# 9_-LPDDR4_SDRAM-1.net
KiCad netlist of a schematic drawn in Altium Designer
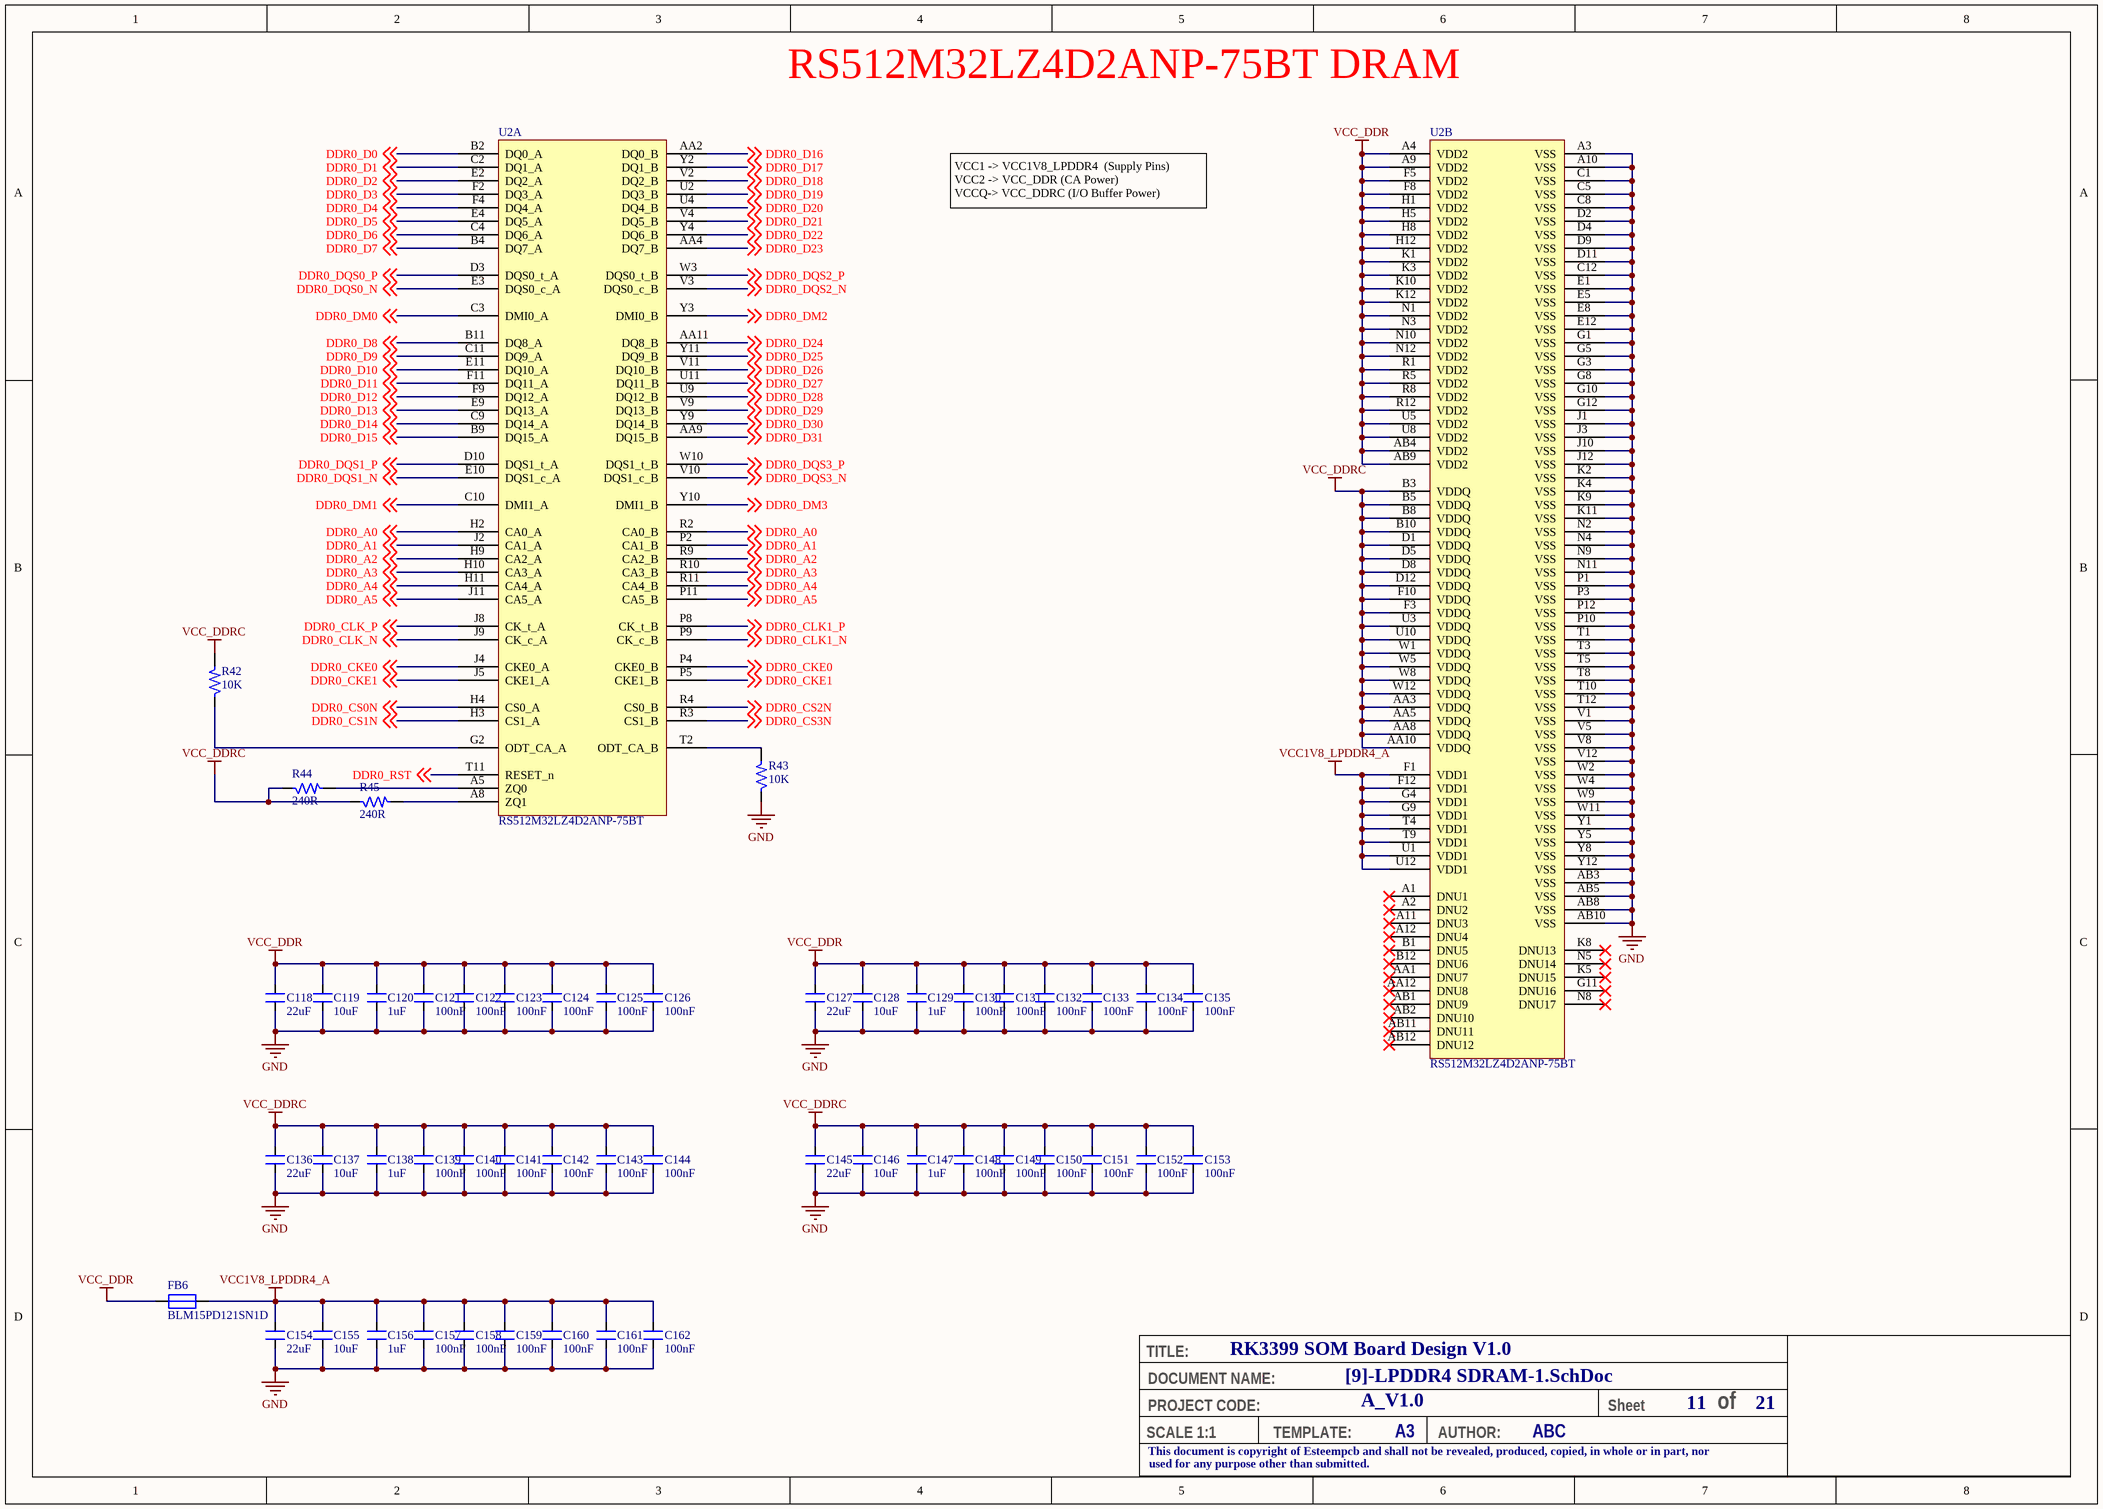
[diagram p0: [9]-LPDDR4 SDRAM-1.SchDoc]

(export (version "E")
  (design (tool "Eeschema 10.0.6"))
  (components
    (comp (ref "C118")
      (value "22uF")
      (footprint "CAP_0402")
      (description "22µF ±20% 6.3V Ceramic Capacitor X5R 0402 (1005 Metric)")
      (fields
        (field (name "MANUFACTURER") "Murata Electronics")
        (field (name "MANUFACTURER PART NUMBER") "CL05A226MQ5N6J8")
      )
      (libsource (lib "RK3399 _Module_Intlib") (part "CAP_22uF-6.3V-20%-0402"))
    )
    (comp (ref "C119")
      (value "10uF")
      (footprint "CAP_0402")
      (description "10µF ±20% 10V Ceramic Capacitor X5R 0402 (1005 Metric)")
      (fields
        (field (name "MANUFACTURER PART NUMBER") "CL05A106MP5NUNC")
        (field (name "MANUFACTURER") "Samsung Electro-Mechanics")
      )
      (libsource (lib "RK3399 _Module_Schlib") (part "CAP_10uF-10V-20%-0402"))
    )
    (comp (ref "C120")
      (value "1uF")
      (footprint "CAP_0201")
      (description "1µF ±20% 16V Ceramic Capacitor X5R 0201 (0603 Metric)")
      (fields
        (field (name "MANUFACTURER") "Samsung Electro-Mechanics")
        (field (name "MANUFACTURER PART NUMBER") "CL03A105MO3NRNH")
      )
      (libsource (lib "RK3399 _Module_Intlib") (part "CAP_1uF-16V-10%-0201"))
    )
    (comp (ref "C121")
      (value "100nF")
      (footprint "CAP_0201")
      (description "0.1µF ±10% 25V Ceramic Capacitor X5R 0201 (0603 Metric)")
      (fields
        (field (name "MANUFACTURER") "TDK Corporation")
        (field (name "MANUFACTURER PART NUMBER") "C0603X5R1E104K030BB")
      )
      (libsource (lib "RK3399 _Module_Intlib") (part "CAP_100nF-25V-10%-0201"))
    )
    (comp (ref "C122")
      (value "100nF")
      (footprint "CAP_0201")
      (description "0.1µF ±10% 25V Ceramic Capacitor X5R 0201 (0603 Metric)")
      (fields
        (field (name "MANUFACTURER") "TDK Corporation")
        (field (name "MANUFACTURER PART NUMBER") "C0603X5R1E104K030BB")
      )
      (libsource (lib "RK3399 _Module_Intlib") (part "CAP_100nF-25V-10%-0201"))
    )
    (comp (ref "C123")
      (value "100nF")
      (footprint "CAP_0201")
      (description "0.1µF ±10% 25V Ceramic Capacitor X5R 0201 (0603 Metric)")
      (fields
        (field (name "MANUFACTURER") "TDK Corporation")
        (field (name "MANUFACTURER PART NUMBER") "C0603X5R1E104K030BB")
      )
      (libsource (lib "RK3399 _Module_Intlib") (part "CAP_100nF-25V-10%-0201"))
    )
    (comp (ref "C124")
      (value "100nF")
      (footprint "CAP_0201")
      (description "0.1µF ±10% 25V Ceramic Capacitor X5R 0201 (0603 Metric)")
      (fields
        (field (name "MANUFACTURER") "TDK Corporation")
        (field (name "MANUFACTURER PART NUMBER") "C0603X5R1E104K030BB")
      )
      (libsource (lib "RK3399 _Module_Intlib") (part "CAP_100nF-25V-10%-0201"))
    )
    (comp (ref "C125")
      (value "100nF")
      (footprint "CAP_0201")
      (description "0.1µF ±10% 25V Ceramic Capacitor X5R 0201 (0603 Metric)")
      (fields
        (field (name "MANUFACTURER") "TDK Corporation")
        (field (name "MANUFACTURER PART NUMBER") "C0603X5R1E104K030BB")
      )
      (libsource (lib "RK3399 _Module_Intlib") (part "CAP_100nF-25V-10%-0201"))
    )
    (comp (ref "C126")
      (value "100nF")
      (footprint "CAP_0201")
      (description "0.1µF ±10% 25V Ceramic Capacitor X5R 0201 (0603 Metric)")
      (fields
        (field (name "MANUFACTURER") "TDK Corporation")
        (field (name "MANUFACTURER PART NUMBER") "C0603X5R1E104K030BB")
      )
      (libsource (lib "RK3399 _Module_Intlib") (part "CAP_100nF-25V-10%-0201"))
    )
    (comp (ref "C127")
      (value "22uF")
      (footprint "CAP_0402")
      (description "22µF ±20% 6.3V Ceramic Capacitor X5R 0402 (1005 Metric)")
      (fields
        (field (name "MANUFACTURER") "Murata Electronics")
        (field (name "MANUFACTURER PART NUMBER") "CL05A226MQ5N6J8")
      )
      (libsource (lib "RK3399 _Module_Intlib") (part "CAP_22uF-6.3V-20%-0402"))
    )
    (comp (ref "C128")
      (value "10uF")
      (footprint "CAP_0402")
      (description "10µF ±20% 10V Ceramic Capacitor X5R 0402 (1005 Metric)")
      (fields
        (field (name "MANUFACTURER PART NUMBER") "CL05A106MP5NUNC")
        (field (name "MANUFACTURER") "Samsung Electro-Mechanics")
      )
      (libsource (lib "RK3399 _Module_Schlib") (part "CAP_10uF-10V-20%-0402"))
    )
    (comp (ref "C129")
      (value "1uF")
      (footprint "CAP_0201")
      (description "1µF ±20% 16V Ceramic Capacitor X5R 0201 (0603 Metric)")
      (fields
        (field (name "MANUFACTURER") "Samsung Electro-Mechanics")
        (field (name "MANUFACTURER PART NUMBER") "CL03A105MO3NRNH")
      )
      (libsource (lib "RK3399 _Module_Intlib") (part "CAP_1uF-16V-10%-0201"))
    )
    (comp (ref "C130")
      (value "100nF")
      (footprint "CAP_0201")
      (description "0.1µF ±10% 25V Ceramic Capacitor X5R 0201 (0603 Metric)")
      (fields
        (field (name "MANUFACTURER") "TDK Corporation")
        (field (name "MANUFACTURER PART NUMBER") "C0603X5R1E104K030BB")
      )
      (libsource (lib "RK3399 _Module_Intlib") (part "CAP_100nF-25V-10%-0201"))
    )
    (comp (ref "C131")
      (value "100nF")
      (footprint "CAP_0201")
      (description "0.1µF ±10% 25V Ceramic Capacitor X5R 0201 (0603 Metric)")
      (fields
        (field (name "MANUFACTURER") "TDK Corporation")
        (field (name "MANUFACTURER PART NUMBER") "C0603X5R1E104K030BB")
      )
      (libsource (lib "RK3399 _Module_Intlib") (part "CAP_100nF-25V-10%-0201"))
    )
    (comp (ref "C132")
      (value "100nF")
      (footprint "CAP_0201")
      (description "0.1µF ±10% 25V Ceramic Capacitor X5R 0201 (0603 Metric)")
      (fields
        (field (name "MANUFACTURER") "TDK Corporation")
        (field (name "MANUFACTURER PART NUMBER") "C0603X5R1E104K030BB")
      )
      (libsource (lib "RK3399 _Module_Intlib") (part "CAP_100nF-25V-10%-0201"))
    )
    (comp (ref "C133")
      (value "100nF")
      (footprint "CAP_0201")
      (description "0.1µF ±10% 25V Ceramic Capacitor X5R 0201 (0603 Metric)")
      (fields
        (field (name "MANUFACTURER") "TDK Corporation")
        (field (name "MANUFACTURER PART NUMBER") "C0603X5R1E104K030BB")
      )
      (libsource (lib "RK3399 _Module_Intlib") (part "CAP_100nF-25V-10%-0201"))
    )
    (comp (ref "C134")
      (value "100nF")
      (footprint "CAP_0201")
      (description "0.1µF ±10% 25V Ceramic Capacitor X5R 0201 (0603 Metric)")
      (fields
        (field (name "MANUFACTURER") "TDK Corporation")
        (field (name "MANUFACTURER PART NUMBER") "C0603X5R1E104K030BB")
      )
      (libsource (lib "RK3399 _Module_Intlib") (part "CAP_100nF-25V-10%-0201"))
    )
    (comp (ref "C135")
      (value "100nF")
      (footprint "CAP_0201")
      (description "0.1µF ±10% 25V Ceramic Capacitor X5R 0201 (0603 Metric)")
      (fields
        (field (name "MANUFACTURER") "TDK Corporation")
        (field (name "MANUFACTURER PART NUMBER") "C0603X5R1E104K030BB")
      )
      (libsource (lib "RK3399 _Module_Intlib") (part "CAP_100nF-25V-10%-0201"))
    )
    (comp (ref "C136")
      (value "22uF")
      (footprint "CAP_0402")
      (description "22µF ±20% 6.3V Ceramic Capacitor X5R 0402 (1005 Metric)")
      (fields
        (field (name "MANUFACTURER") "Murata Electronics")
        (field (name "MANUFACTURER PART NUMBER") "CL05A226MQ5N6J8")
      )
      (libsource (lib "RK3399 _Module_Intlib") (part "CAP_22uF-6.3V-20%-0402"))
    )
    (comp (ref "C137")
      (value "10uF")
      (footprint "CAP_0402")
      (description "10µF ±20% 10V Ceramic Capacitor X5R 0402 (1005 Metric)")
      (fields
        (field (name "MANUFACTURER PART NUMBER") "CL05A106MP5NUNC")
        (field (name "MANUFACTURER") "Samsung Electro-Mechanics")
      )
      (libsource (lib "RK3399 _Module_Schlib") (part "CAP_10uF-10V-20%-0402"))
    )
    (comp (ref "C138")
      (value "1uF")
      (footprint "CAP_0201")
      (description "1µF ±20% 16V Ceramic Capacitor X5R 0201 (0603 Metric)")
      (fields
        (field (name "MANUFACTURER") "Samsung Electro-Mechanics")
        (field (name "MANUFACTURER PART NUMBER") "CL03A105MO3NRNH")
      )
      (libsource (lib "RK3399 _Module_Intlib") (part "CAP_1uF-16V-10%-0201"))
    )
    (comp (ref "C139")
      (value "100nF")
      (footprint "CAP_0201")
      (description "0.1µF ±10% 25V Ceramic Capacitor X5R 0201 (0603 Metric)")
      (fields
        (field (name "MANUFACTURER") "TDK Corporation")
        (field (name "MANUFACTURER PART NUMBER") "C0603X5R1E104K030BB")
      )
      (libsource (lib "RK3399 _Module_Intlib") (part "CAP_100nF-25V-10%-0201"))
    )
    (comp (ref "C140")
      (value "100nF")
      (footprint "CAP_0201")
      (description "0.1µF ±10% 25V Ceramic Capacitor X5R 0201 (0603 Metric)")
      (fields
        (field (name "MANUFACTURER") "TDK Corporation")
        (field (name "MANUFACTURER PART NUMBER") "C0603X5R1E104K030BB")
      )
      (libsource (lib "RK3399 _Module_Intlib") (part "CAP_100nF-25V-10%-0201"))
    )
    (comp (ref "C141")
      (value "100nF")
      (footprint "CAP_0201")
      (description "0.1µF ±10% 25V Ceramic Capacitor X5R 0201 (0603 Metric)")
      (fields
        (field (name "MANUFACTURER") "TDK Corporation")
        (field (name "MANUFACTURER PART NUMBER") "C0603X5R1E104K030BB")
      )
      (libsource (lib "RK3399 _Module_Intlib") (part "CAP_100nF-25V-10%-0201"))
    )
    (comp (ref "C142")
      (value "100nF")
      (footprint "CAP_0201")
      (description "0.1µF ±10% 25V Ceramic Capacitor X5R 0201 (0603 Metric)")
      (fields
        (field (name "MANUFACTURER") "TDK Corporation")
        (field (name "MANUFACTURER PART NUMBER") "C0603X5R1E104K030BB")
      )
      (libsource (lib "RK3399 _Module_Intlib") (part "CAP_100nF-25V-10%-0201"))
    )
    (comp (ref "C143")
      (value "100nF")
      (footprint "CAP_0201")
      (description "0.1µF ±10% 25V Ceramic Capacitor X5R 0201 (0603 Metric)")
      (fields
        (field (name "MANUFACTURER") "TDK Corporation")
        (field (name "MANUFACTURER PART NUMBER") "C0603X5R1E104K030BB")
      )
      (libsource (lib "RK3399 _Module_Intlib") (part "CAP_100nF-25V-10%-0201"))
    )
    (comp (ref "C144")
      (value "100nF")
      (footprint "CAP_0201")
      (description "0.1µF ±10% 25V Ceramic Capacitor X5R 0201 (0603 Metric)")
      (fields
        (field (name "MANUFACTURER") "TDK Corporation")
        (field (name "MANUFACTURER PART NUMBER") "C0603X5R1E104K030BB")
      )
      (libsource (lib "RK3399 _Module_Intlib") (part "CAP_100nF-25V-10%-0201"))
    )
    (comp (ref "C145")
      (value "22uF")
      (footprint "CAP_0402")
      (description "22µF ±20% 6.3V Ceramic Capacitor X5R 0402 (1005 Metric)")
      (fields
        (field (name "MANUFACTURER") "Murata Electronics")
        (field (name "MANUFACTURER PART NUMBER") "CL05A226MQ5N6J8")
      )
      (libsource (lib "RK3399 _Module_Intlib") (part "CAP_22uF-6.3V-20%-0402"))
    )
    (comp (ref "C146")
      (value "10uF")
      (footprint "CAP_0402")
      (description "10µF ±20% 10V Ceramic Capacitor X5R 0402 (1005 Metric)")
      (fields
        (field (name "MANUFACTURER PART NUMBER") "CL05A106MP5NUNC")
        (field (name "MANUFACTURER") "Samsung Electro-Mechanics")
      )
      (libsource (lib "RK3399 _Module_Schlib") (part "CAP_10uF-10V-20%-0402"))
    )
    (comp (ref "C147")
      (value "1uF")
      (footprint "CAP_0201")
      (description "1µF ±20% 16V Ceramic Capacitor X5R 0201 (0603 Metric)")
      (fields
        (field (name "MANUFACTURER") "Samsung Electro-Mechanics")
        (field (name "MANUFACTURER PART NUMBER") "CL03A105MO3NRNH")
      )
      (libsource (lib "RK3399 _Module_Intlib") (part "CAP_1uF-16V-10%-0201"))
    )
    (comp (ref "C148")
      (value "100nF")
      (footprint "CAP_0201")
      (description "0.1µF ±10% 25V Ceramic Capacitor X5R 0201 (0603 Metric)")
      (fields
        (field (name "MANUFACTURER") "TDK Corporation")
        (field (name "MANUFACTURER PART NUMBER") "C0603X5R1E104K030BB")
      )
      (libsource (lib "RK3399 _Module_Intlib") (part "CAP_100nF-25V-10%-0201"))
    )
    (comp (ref "C149")
      (value "100nF")
      (footprint "CAP_0201")
      (description "0.1µF ±10% 25V Ceramic Capacitor X5R 0201 (0603 Metric)")
      (fields
        (field (name "MANUFACTURER") "TDK Corporation")
        (field (name "MANUFACTURER PART NUMBER") "C0603X5R1E104K030BB")
      )
      (libsource (lib "RK3399 _Module_Intlib") (part "CAP_100nF-25V-10%-0201"))
    )
    (comp (ref "C150")
      (value "100nF")
      (footprint "CAP_0201")
      (description "0.1µF ±10% 25V Ceramic Capacitor X5R 0201 (0603 Metric)")
      (fields
        (field (name "MANUFACTURER") "TDK Corporation")
        (field (name "MANUFACTURER PART NUMBER") "C0603X5R1E104K030BB")
      )
      (libsource (lib "RK3399 _Module_Intlib") (part "CAP_100nF-25V-10%-0201"))
    )
    (comp (ref "C151")
      (value "100nF")
      (footprint "CAP_0201")
      (description "0.1µF ±10% 25V Ceramic Capacitor X5R 0201 (0603 Metric)")
      (fields
        (field (name "MANUFACTURER") "TDK Corporation")
        (field (name "MANUFACTURER PART NUMBER") "C0603X5R1E104K030BB")
      )
      (libsource (lib "RK3399 _Module_Intlib") (part "CAP_100nF-25V-10%-0201"))
    )
    (comp (ref "C152")
      (value "100nF")
      (footprint "CAP_0201")
      (description "0.1µF ±10% 25V Ceramic Capacitor X5R 0201 (0603 Metric)")
      (fields
        (field (name "MANUFACTURER") "TDK Corporation")
        (field (name "MANUFACTURER PART NUMBER") "C0603X5R1E104K030BB")
      )
      (libsource (lib "RK3399 _Module_Intlib") (part "CAP_100nF-25V-10%-0201"))
    )
    (comp (ref "C153")
      (value "100nF")
      (footprint "CAP_0201")
      (description "0.1µF ±10% 25V Ceramic Capacitor X5R 0201 (0603 Metric)")
      (fields
        (field (name "MANUFACTURER") "TDK Corporation")
        (field (name "MANUFACTURER PART NUMBER") "C0603X5R1E104K030BB")
      )
      (libsource (lib "RK3399 _Module_Intlib") (part "CAP_100nF-25V-10%-0201"))
    )
    (comp (ref "C154")
      (value "22uF")
      (footprint "CAP_0402")
      (description "22µF ±20% 6.3V Ceramic Capacitor X5R 0402 (1005 Metric)")
      (fields
        (field (name "MANUFACTURER") "Murata Electronics")
        (field (name "MANUFACTURER PART NUMBER") "CL05A226MQ5N6J8")
      )
      (libsource (lib "RK3399 _Module_Intlib") (part "CAP_22uF-6.3V-20%-0402"))
    )
    (comp (ref "C155")
      (value "10uF")
      (footprint "CAP_0402")
      (description "10µF ±20% 10V Ceramic Capacitor X5R 0402 (1005 Metric)")
      (fields
        (field (name "MANUFACTURER PART NUMBER") "CL05A106MP5NUNC")
        (field (name "MANUFACTURER") "Samsung Electro-Mechanics")
      )
      (libsource (lib "RK3399 _Module_Schlib") (part "CAP_10uF-10V-20%-0402"))
    )
    (comp (ref "C156")
      (value "1uF")
      (footprint "CAP_0201")
      (description "1µF ±20% 16V Ceramic Capacitor X5R 0201 (0603 Metric)")
      (fields
        (field (name "MANUFACTURER") "Samsung Electro-Mechanics")
        (field (name "MANUFACTURER PART NUMBER") "CL03A105MO3NRNH")
      )
      (libsource (lib "RK3399 _Module_Intlib") (part "CAP_1uF-16V-10%-0201"))
    )
    (comp (ref "C157")
      (value "100nF")
      (footprint "CAP_0201")
      (description "0.1µF ±10% 25V Ceramic Capacitor X5R 0201 (0603 Metric)")
      (fields
        (field (name "MANUFACTURER") "TDK Corporation")
        (field (name "MANUFACTURER PART NUMBER") "C0603X5R1E104K030BB")
      )
      (libsource (lib "RK3399 _Module_Intlib") (part "CAP_100nF-25V-10%-0201"))
    )
    (comp (ref "C158")
      (value "100nF")
      (footprint "CAP_0201")
      (description "0.1µF ±10% 25V Ceramic Capacitor X5R 0201 (0603 Metric)")
      (fields
        (field (name "MANUFACTURER") "TDK Corporation")
        (field (name "MANUFACTURER PART NUMBER") "C0603X5R1E104K030BB")
      )
      (libsource (lib "RK3399 _Module_Intlib") (part "CAP_100nF-25V-10%-0201"))
    )
    (comp (ref "C159")
      (value "100nF")
      (footprint "CAP_0201")
      (description "0.1µF ±10% 25V Ceramic Capacitor X5R 0201 (0603 Metric)")
      (fields
        (field (name "MANUFACTURER") "TDK Corporation")
        (field (name "MANUFACTURER PART NUMBER") "C0603X5R1E104K030BB")
      )
      (libsource (lib "RK3399 _Module_Intlib") (part "CAP_100nF-25V-10%-0201"))
    )
    (comp (ref "C160")
      (value "100nF")
      (footprint "CAP_0201")
      (description "0.1µF ±10% 25V Ceramic Capacitor X5R 0201 (0603 Metric)")
      (fields
        (field (name "MANUFACTURER") "TDK Corporation")
        (field (name "MANUFACTURER PART NUMBER") "C0603X5R1E104K030BB")
      )
      (libsource (lib "RK3399 _Module_Intlib") (part "CAP_100nF-25V-10%-0201"))
    )
    (comp (ref "C161")
      (value "100nF")
      (footprint "CAP_0201")
      (description "0.1µF ±10% 25V Ceramic Capacitor X5R 0201 (0603 Metric)")
      (fields
        (field (name "MANUFACTURER") "TDK Corporation")
        (field (name "MANUFACTURER PART NUMBER") "C0603X5R1E104K030BB")
      )
      (libsource (lib "RK3399 _Module_Intlib") (part "CAP_100nF-25V-10%-0201"))
    )
    (comp (ref "C162")
      (value "100nF")
      (footprint "CAP_0201")
      (description "0.1µF ±10% 25V Ceramic Capacitor X5R 0201 (0603 Metric)")
      (fields
        (field (name "MANUFACTURER") "TDK Corporation")
        (field (name "MANUFACTURER PART NUMBER") "C0603X5R1E104K030BB")
      )
      (libsource (lib "RK3399 _Module_Intlib") (part "CAP_100nF-25V-10%-0201"))
    )
    (comp (ref "FB6")
      (value "BLM15PD121SN1D")
      (footprint "RES_0402")
      (description "120 Ohms @ 100MHz 1 Power Line Ferrite Bead 0402 (1005 Metric) 1.3A 90mOhm")
      (fields (field (name "MANUFACTURER") "Murata Electronics"))
      (libsource (lib "RK3399 _Module_Schlib") (part "FB_120R-1.3A-100Mhz-0402"))
    )
    (comp (ref "R42")
      (value "10K")
      (footprint "RES_0201")
      (description "10 kOhms ±1% 0.05W, 1/20W Chip Resistor 0201 (0603 Metric) Thick Film")
      (fields
        (field (name "MANUFACTURER") "Stackpole Electronics Inc")
        (field (name "MANUFACTURER PART NUMBER") "RMCF0201FT10K0")
      )
      (libsource (lib "RK3399 _Module_Intlib") (part "RES_10K-0.05W-1%-0201"))
    )
    (comp (ref "R43")
      (value "10K")
      (footprint "RES_0201")
      (description "10 kOhms ±1% 0.05W, 1/20W Chip Resistor 0201 (0603 Metric) Thick Film")
      (fields
        (field (name "MANUFACTURER") "Stackpole Electronics Inc")
        (field (name "MANUFACTURER PART NUMBER") "RMCF0201FT10K0")
      )
      (libsource (lib "RK3399 _Module_Intlib") (part "RES_10K-0.05W-1%-0201"))
    )
    (comp (ref "R44")
      (value "240R")
      (footprint "RES_0201")
      (description "240 Ohms ±1% 0.05W, 1/20W Chip Resistor 0201 (0603 Metric) Thick Film")
      (fields
        (field (name "MANUFACTURER") "Yageo")
        (field (name "MANUFACTURER PART NUMBER") "RC0201FR-07240RL")
      )
      (libsource (lib "RK3399 _Module_Intlib") (part "RES_240R-0.05W-1%-0201"))
    )
    (comp (ref "R45")
      (value "240R")
      (footprint "RES_0201")
      (description "240 Ohms ±1% 0.05W, 1/20W Chip Resistor 0201 (0603 Metric) Thick Film")
      (fields
        (field (name "MANUFACTURER") "Yageo")
        (field (name "MANUFACTURER PART NUMBER") "RC0201FR-07240RL")
      )
      (libsource (lib "RK3399 _Module_Intlib") (part "RES_240R-0.05W-1%-0201"))
    )
    (comp (ref "U2")
      (value "RS512M32LZ4D2ANP-75BT")
      (footprint "FBGA200_SMD")
      (fields (field (name "MANUFACTURER") "RAYSON"))
      (libsource (lib "RK3399 _Module_Schlib") (part "IC_RS512M32LZ4D2ANP-75BT"))
    )
  )
  (nets
    (net (code "1") (name "DDR0_A0") (class "Default")
      (node (ref "U2") (pin "H2") (pinfunction "CA0_A_H2") (pintype "passive"))
      (node (ref "U2") (pin "R2") (pinfunction "CA0_B_R2") (pintype "passive"))
    )
    (net (code "2") (name "DDR0_A1") (class "Default")
      (node (ref "U2") (pin "J2") (pinfunction "CA1_A_J2") (pintype "passive"))
      (node (ref "U2") (pin "P2") (pinfunction "CA1_B_P2") (pintype "passive"))
    )
    (net (code "3") (name "DDR0_A2") (class "Default")
      (node (ref "U2") (pin "H9") (pinfunction "CA2_A_H9") (pintype "passive"))
      (node (ref "U2") (pin "R9") (pinfunction "CA2_B_R9") (pintype "passive"))
    )
    (net (code "4") (name "DDR0_A3") (class "Default")
      (node (ref "U2") (pin "H10") (pinfunction "CA3_A_H10") (pintype "passive"))
      (node (ref "U2") (pin "R10") (pinfunction "CA3_B_R10") (pintype "passive"))
    )
    (net (code "5") (name "DDR0_A4") (class "Default")
      (node (ref "U2") (pin "H11") (pinfunction "CA4_A_H11") (pintype "passive"))
      (node (ref "U2") (pin "R11") (pinfunction "CA4_B_R11") (pintype "passive"))
    )
    (net (code "6") (name "DDR0_A5") (class "Default")
      (node (ref "U2") (pin "J11") (pinfunction "CA5_A_J11") (pintype "passive"))
      (node (ref "U2") (pin "P11") (pinfunction "CA5_B_P11") (pintype "passive"))
    )
    (net (code "7") (name "DDR0_CKE0") (class "Default")
      (node (ref "U2") (pin "J4") (pinfunction "CKE0_A_J4") (pintype "passive"))
      (node (ref "U2") (pin "P4") (pinfunction "CKE0_B_P4") (pintype "passive"))
    )
    (net (code "8") (name "DDR0_CKE1") (class "Default")
      (node (ref "U2") (pin "J5") (pinfunction "CKE1_A_J5") (pintype "passive"))
      (node (ref "U2") (pin "P5") (pinfunction "CKE1_B_P5") (pintype "passive"))
    )
    (net (code "9") (name "DDR0_CLK1_N") (class "Default")
      (node (ref "U2") (pin "P9") (pinfunction "CK_c_B_P9") (pintype "passive"))
    )
    (net (code "10") (name "DDR0_CLK1_P") (class "Default")
      (node (ref "U2") (pin "P8") (pinfunction "CK_t_B_P8") (pintype "passive"))
    )
    (net (code "11") (name "DDR0_CLK_N") (class "Default")
      (node (ref "U2") (pin "J9") (pinfunction "CK_c_A_J9") (pintype "passive"))
    )
    (net (code "12") (name "DDR0_CLK_P") (class "Default")
      (node (ref "U2") (pin "J8") (pinfunction "CK_t_A_J8") (pintype "passive"))
    )
    (net (code "13") (name "DDR0_CS0N") (class "Default")
      (node (ref "U2") (pin "H4") (pinfunction "CS0_A_H4") (pintype "passive"))
    )
    (net (code "14") (name "DDR0_CS1N") (class "Default")
      (node (ref "U2") (pin "H3") (pinfunction "CS1_A_H3") (pintype "passive"))
    )
    (net (code "15") (name "DDR0_CS2N") (class "Default")
      (node (ref "U2") (pin "R4") (pinfunction "CS0_B_R4") (pintype "passive"))
    )
    (net (code "16") (name "DDR0_CS3N") (class "Default")
      (node (ref "U2") (pin "R3") (pinfunction "CS1_B_R3") (pintype "passive"))
    )
    (net (code "17") (name "DDR0_D0") (class "Default")
      (node (ref "U2") (pin "B2") (pinfunction "DQ0_A_B2") (pintype "passive"))
    )
    (net (code "18") (name "DDR0_D1") (class "Default")
      (node (ref "U2") (pin "C2") (pinfunction "DQ1_A_C2") (pintype "passive"))
    )
    (net (code "19") (name "DDR0_D2") (class "Default")
      (node (ref "U2") (pin "E2") (pinfunction "DQ2_A_E2") (pintype "passive"))
    )
    (net (code "20") (name "DDR0_D3") (class "Default")
      (node (ref "U2") (pin "F2") (pinfunction "DQ3_A_F2") (pintype "passive"))
    )
    (net (code "21") (name "DDR0_D4") (class "Default")
      (node (ref "U2") (pin "F4") (pinfunction "DQ4_A_F4") (pintype "passive"))
    )
    (net (code "22") (name "DDR0_D5") (class "Default")
      (node (ref "U2") (pin "E4") (pinfunction "DQ5_A_E4") (pintype "passive"))
    )
    (net (code "23") (name "DDR0_D6") (class "Default")
      (node (ref "U2") (pin "C4") (pinfunction "DQ6_A_C4") (pintype "passive"))
    )
    (net (code "24") (name "DDR0_D7") (class "Default")
      (node (ref "U2") (pin "B4") (pinfunction "DQ7_A_B4") (pintype "passive"))
    )
    (net (code "25") (name "DDR0_D8") (class "Default")
      (node (ref "U2") (pin "B11") (pinfunction "DQ8_A_B11") (pintype "passive"))
    )
    (net (code "26") (name "DDR0_D9") (class "Default")
      (node (ref "U2") (pin "C11") (pinfunction "DQ9_A_C11") (pintype "passive"))
    )
    (net (code "27") (name "DDR0_D10") (class "Default")
      (node (ref "U2") (pin "E11") (pinfunction "DQ10_A_E11") (pintype "passive"))
    )
    (net (code "28") (name "DDR0_D11") (class "Default")
      (node (ref "U2") (pin "F11") (pinfunction "DQ11_A_F11") (pintype "passive"))
    )
    (net (code "29") (name "DDR0_D12") (class "Default")
      (node (ref "U2") (pin "F9") (pinfunction "DQ12_A_F9") (pintype "passive"))
    )
    (net (code "30") (name "DDR0_D13") (class "Default")
      (node (ref "U2") (pin "E9") (pinfunction "DQ13_A_E9") (pintype "passive"))
    )
    (net (code "31") (name "DDR0_D14") (class "Default")
      (node (ref "U2") (pin "C9") (pinfunction "DQ14_A_C9") (pintype "passive"))
    )
    (net (code "32") (name "DDR0_D15") (class "Default")
      (node (ref "U2") (pin "B9") (pinfunction "DQ15_A_B9") (pintype "passive"))
    )
    (net (code "33") (name "DDR0_D16") (class "Default")
      (node (ref "U2") (pin "AA2") (pinfunction "DQ0_B_AA2") (pintype "passive"))
    )
    (net (code "34") (name "DDR0_D17") (class "Default")
      (node (ref "U2") (pin "Y2") (pinfunction "DQ1_B_Y2") (pintype "passive"))
    )
    (net (code "35") (name "DDR0_D18") (class "Default")
      (node (ref "U2") (pin "V2") (pinfunction "DQ2_B_V2") (pintype "passive"))
    )
    (net (code "36") (name "DDR0_D19") (class "Default")
      (node (ref "U2") (pin "U2") (pinfunction "DQ3_B_U2") (pintype "passive"))
    )
    (net (code "37") (name "DDR0_D20") (class "Default")
      (node (ref "U2") (pin "U4") (pinfunction "DQ4_B_U4") (pintype "passive"))
    )
    (net (code "38") (name "DDR0_D21") (class "Default")
      (node (ref "U2") (pin "V4") (pinfunction "DQ5_B_V4") (pintype "passive"))
    )
    (net (code "39") (name "DDR0_D22") (class "Default")
      (node (ref "U2") (pin "Y4") (pinfunction "DQ6_B_Y4") (pintype "passive"))
    )
    (net (code "40") (name "DDR0_D23") (class "Default")
      (node (ref "U2") (pin "AA4") (pinfunction "DQ7_B_AA4") (pintype "passive"))
    )
    (net (code "41") (name "DDR0_D24") (class "Default")
      (node (ref "U2") (pin "AA11") (pinfunction "DQ8_B_AA11") (pintype "passive"))
    )
    (net (code "42") (name "DDR0_D25") (class "Default")
      (node (ref "U2") (pin "Y11") (pinfunction "DQ9_B_Y11") (pintype "passive"))
    )
    (net (code "43") (name "DDR0_D26") (class "Default")
      (node (ref "U2") (pin "V11") (pinfunction "DQ10_B_V11") (pintype "passive"))
    )
    (net (code "44") (name "DDR0_D27") (class "Default")
      (node (ref "U2") (pin "U11") (pinfunction "DQ11_B_U11") (pintype "passive"))
    )
    (net (code "45") (name "DDR0_D28") (class "Default")
      (node (ref "U2") (pin "U9") (pinfunction "DQ12_B_U9") (pintype "passive"))
    )
    (net (code "46") (name "DDR0_D29") (class "Default")
      (node (ref "U2") (pin "V9") (pinfunction "DQ13_B_V9") (pintype "passive"))
    )
    (net (code "47") (name "DDR0_D30") (class "Default")
      (node (ref "U2") (pin "Y9") (pinfunction "DQ14_B_Y9") (pintype "passive"))
    )
    (net (code "48") (name "DDR0_D31") (class "Default")
      (node (ref "U2") (pin "AA9") (pinfunction "DQ15_B_AA9") (pintype "passive"))
    )
    (net (code "49") (name "DDR0_DM0") (class "Default")
      (node (ref "U2") (pin "C3") (pinfunction "DMI0_A_C3") (pintype "passive"))
    )
    (net (code "50") (name "DDR0_DM1") (class "Default")
      (node (ref "U2") (pin "C10") (pinfunction "DMI1_A_C10") (pintype "passive"))
    )
    (net (code "51") (name "DDR0_DM2") (class "Default")
      (node (ref "U2") (pin "Y3") (pinfunction "DMI0_B_Y3") (pintype "passive"))
    )
    (net (code "52") (name "DDR0_DM3") (class "Default")
      (node (ref "U2") (pin "Y10") (pinfunction "DMI1_B_Y10") (pintype "passive"))
    )
    (net (code "53") (name "DDR0_DQS0_N") (class "Default")
      (node (ref "U2") (pin "E3") (pinfunction "DQS0_c_A_E3") (pintype "passive"))
    )
    (net (code "54") (name "DDR0_DQS0_P") (class "Default")
      (node (ref "U2") (pin "D3") (pinfunction "DQS0_t_A_D3") (pintype "passive"))
    )
    (net (code "55") (name "DDR0_DQS1_N") (class "Default")
      (node (ref "U2") (pin "E10") (pinfunction "DQS1_c_A_E10") (pintype "passive"))
    )
    (net (code "56") (name "DDR0_DQS1_P") (class "Default")
      (node (ref "U2") (pin "D10") (pinfunction "DQS1_t_A_D10") (pintype "passive"))
    )
    (net (code "57") (name "DDR0_DQS2_N") (class "Default")
      (node (ref "U2") (pin "V3") (pinfunction "DQS0_c_B_V3") (pintype "passive"))
    )
    (net (code "58") (name "DDR0_DQS2_P") (class "Default")
      (node (ref "U2") (pin "W3") (pinfunction "DQS0_t_B_W3") (pintype "passive"))
    )
    (net (code "59") (name "DDR0_DQS3_N") (class "Default")
      (node (ref "U2") (pin "V10") (pinfunction "DQS1_c_B_V10") (pintype "passive"))
    )
    (net (code "60") (name "DDR0_DQS3_P") (class "Default")
      (node (ref "U2") (pin "W10") (pinfunction "DQS1_t_B_W10") (pintype "passive"))
    )
    (net (code "61") (name "DDR0_RST") (class "Default")
      (node (ref "U2") (pin "T11") (pinfunction "RESET_n_T11") (pintype "passive"))
    )
    (net (code "62") (name "GND") (class "Default")
      (node (ref "C118") (pin "1") (pinfunction "1_1") (pintype "passive"))
      (node (ref "C119") (pin "1") (pinfunction "1_1") (pintype "passive"))
      (node (ref "C120") (pin "1") (pinfunction "1_1") (pintype "passive"))
      (node (ref "C121") (pin "1") (pinfunction "1_1") (pintype "passive"))
      (node (ref "C122") (pin "1") (pinfunction "1_1") (pintype "passive"))
      (node (ref "C123") (pin "1") (pinfunction "1_1") (pintype "passive"))
      (node (ref "C124") (pin "1") (pinfunction "1_1") (pintype "passive"))
      (node (ref "C125") (pin "1") (pinfunction "1_1") (pintype "passive"))
      (node (ref "C126") (pin "1") (pinfunction "1_1") (pintype "passive"))
      (node (ref "C127") (pin "1") (pinfunction "1_1") (pintype "passive"))
      (node (ref "C128") (pin "1") (pinfunction "1_1") (pintype "passive"))
      (node (ref "C129") (pin "1") (pinfunction "1_1") (pintype "passive"))
      (node (ref "C130") (pin "1") (pinfunction "1_1") (pintype "passive"))
      (node (ref "C131") (pin "1") (pinfunction "1_1") (pintype "passive"))
      (node (ref "C132") (pin "1") (pinfunction "1_1") (pintype "passive"))
      (node (ref "C133") (pin "1") (pinfunction "1_1") (pintype "passive"))
      (node (ref "C134") (pin "1") (pinfunction "1_1") (pintype "passive"))
      (node (ref "C135") (pin "1") (pinfunction "1_1") (pintype "passive"))
      (node (ref "C136") (pin "1") (pinfunction "1_1") (pintype "passive"))
      (node (ref "C137") (pin "1") (pinfunction "1_1") (pintype "passive"))
      (node (ref "C138") (pin "1") (pinfunction "1_1") (pintype "passive"))
      (node (ref "C139") (pin "1") (pinfunction "1_1") (pintype "passive"))
      (node (ref "C140") (pin "1") (pinfunction "1_1") (pintype "passive"))
      (node (ref "C141") (pin "1") (pinfunction "1_1") (pintype "passive"))
      (node (ref "C142") (pin "1") (pinfunction "1_1") (pintype "passive"))
      (node (ref "C143") (pin "1") (pinfunction "1_1") (pintype "passive"))
      (node (ref "C144") (pin "1") (pinfunction "1_1") (pintype "passive"))
      (node (ref "C145") (pin "1") (pinfunction "1_1") (pintype "passive"))
      (node (ref "C146") (pin "1") (pinfunction "1_1") (pintype "passive"))
      (node (ref "C147") (pin "1") (pinfunction "1_1") (pintype "passive"))
      (node (ref "C148") (pin "1") (pinfunction "1_1") (pintype "passive"))
      (node (ref "C149") (pin "1") (pinfunction "1_1") (pintype "passive"))
      (node (ref "C150") (pin "1") (pinfunction "1_1") (pintype "passive"))
      (node (ref "C151") (pin "1") (pinfunction "1_1") (pintype "passive"))
      (node (ref "C152") (pin "1") (pinfunction "1_1") (pintype "passive"))
      (node (ref "C153") (pin "1") (pinfunction "1_1") (pintype "passive"))
      (node (ref "C154") (pin "1") (pinfunction "1_1") (pintype "passive"))
      (node (ref "C155") (pin "1") (pinfunction "1_1") (pintype "passive"))
      (node (ref "C156") (pin "1") (pinfunction "1_1") (pintype "passive"))
      (node (ref "C157") (pin "1") (pinfunction "1_1") (pintype "passive"))
      (node (ref "C158") (pin "1") (pinfunction "1_1") (pintype "passive"))
      (node (ref "C159") (pin "1") (pinfunction "1_1") (pintype "passive"))
      (node (ref "C160") (pin "1") (pinfunction "1_1") (pintype "passive"))
      (node (ref "C161") (pin "1") (pinfunction "1_1") (pintype "passive"))
      (node (ref "C162") (pin "1") (pinfunction "1_1") (pintype "passive"))
      (node (ref "R43") (pin "1") (pinfunction "1_1") (pintype "passive"))
      (node (ref "U2") (pin "A10") (pinfunction "VSS_A10") (pintype "passive"))
      (node (ref "U2") (pin "A3") (pinfunction "VSS_A3") (pintype "passive"))
      (node (ref "U2") (pin "AB10") (pinfunction "VSS_AB10") (pintype "passive"))
      (node (ref "U2") (pin "AB3") (pinfunction "VSS_AB3") (pintype "passive"))
      (node (ref "U2") (pin "AB5") (pinfunction "VSS_AB5") (pintype "passive"))
      (node (ref "U2") (pin "AB8") (pinfunction "VSS_AB8") (pintype "passive"))
      (node (ref "U2") (pin "C1") (pinfunction "VSS_C1") (pintype "passive"))
      (node (ref "U2") (pin "C12") (pinfunction "VSS_C12") (pintype "passive"))
      (node (ref "U2") (pin "C5") (pinfunction "VSS_C5") (pintype "passive"))
      (node (ref "U2") (pin "C8") (pinfunction "VSS_C8") (pintype "passive"))
      (node (ref "U2") (pin "D11") (pinfunction "VSS_D11") (pintype "passive"))
      (node (ref "U2") (pin "D2") (pinfunction "VSS_D2") (pintype "passive"))
      (node (ref "U2") (pin "D4") (pinfunction "VSS_D4") (pintype "passive"))
      (node (ref "U2") (pin "D9") (pinfunction "VSS_D9") (pintype "passive"))
      (node (ref "U2") (pin "E1") (pinfunction "VSS_E1") (pintype "passive"))
      (node (ref "U2") (pin "E12") (pinfunction "VSS_E12") (pintype "passive"))
      (node (ref "U2") (pin "E5") (pinfunction "VSS_E5") (pintype "passive"))
      (node (ref "U2") (pin "E8") (pinfunction "VSS_E8") (pintype "passive"))
      (node (ref "U2") (pin "G1") (pinfunction "VSS_G1") (pintype "passive"))
      (node (ref "U2") (pin "G10") (pinfunction "VSS_G10") (pintype "passive"))
      (node (ref "U2") (pin "G12") (pinfunction "VSS_G12") (pintype "passive"))
      (node (ref "U2") (pin "G3") (pinfunction "VSS_G3") (pintype "passive"))
      (node (ref "U2") (pin "G5") (pinfunction "VSS_G5") (pintype "passive"))
      (node (ref "U2") (pin "G8") (pinfunction "VSS_G8") (pintype "passive"))
      (node (ref "U2") (pin "J1") (pinfunction "VSS_J1") (pintype "passive"))
      (node (ref "U2") (pin "J10") (pinfunction "VSS_J10") (pintype "passive"))
      (node (ref "U2") (pin "J12") (pinfunction "VSS_J12") (pintype "passive"))
      (node (ref "U2") (pin "J3") (pinfunction "VSS_J3") (pintype "passive"))
      (node (ref "U2") (pin "K11") (pinfunction "VSS_K11") (pintype "passive"))
      (node (ref "U2") (pin "K2") (pinfunction "VSS_K2") (pintype "passive"))
      (node (ref "U2") (pin "K4") (pinfunction "VSS_K4") (pintype "passive"))
      (node (ref "U2") (pin "K9") (pinfunction "VSS_K9") (pintype "passive"))
      (node (ref "U2") (pin "N11") (pinfunction "VSS_N11") (pintype "passive"))
      (node (ref "U2") (pin "N2") (pinfunction "VSS_N2") (pintype "passive"))
      (node (ref "U2") (pin "N4") (pinfunction "VSS_N4") (pintype "passive"))
      (node (ref "U2") (pin "N9") (pinfunction "VSS_N9") (pintype "passive"))
      (node (ref "U2") (pin "P1") (pinfunction "VSS_P1") (pintype "passive"))
      (node (ref "U2") (pin "P10") (pinfunction "VSS_P10") (pintype "passive"))
      (node (ref "U2") (pin "P12") (pinfunction "VSS_P12") (pintype "passive"))
      (node (ref "U2") (pin "P3") (pinfunction "VSS_P3") (pintype "passive"))
      (node (ref "U2") (pin "T1") (pinfunction "VSS_T1") (pintype "passive"))
      (node (ref "U2") (pin "T10") (pinfunction "VSS_T10") (pintype "passive"))
      (node (ref "U2") (pin "T12") (pinfunction "VSS_T12") (pintype "passive"))
      (node (ref "U2") (pin "T3") (pinfunction "VSS_T3") (pintype "passive"))
      (node (ref "U2") (pin "T5") (pinfunction "VSS_T5") (pintype "passive"))
      (node (ref "U2") (pin "T8") (pinfunction "VSS_T8") (pintype "passive"))
      (node (ref "U2") (pin "V1") (pinfunction "VSS_V1") (pintype "passive"))
      (node (ref "U2") (pin "V12") (pinfunction "VSS_V12") (pintype "passive"))
      (node (ref "U2") (pin "V5") (pinfunction "VSS_V5") (pintype "passive"))
      (node (ref "U2") (pin "V8") (pinfunction "VSS_V8") (pintype "passive"))
      (node (ref "U2") (pin "W11") (pinfunction "VSS_W11") (pintype "passive"))
      (node (ref "U2") (pin "W2") (pinfunction "VSS_W2") (pintype "passive"))
      (node (ref "U2") (pin "W4") (pinfunction "VSS_W4") (pintype "passive"))
      (node (ref "U2") (pin "W9") (pinfunction "VSS_W9") (pintype "passive"))
      (node (ref "U2") (pin "Y1") (pinfunction "VSS_Y1") (pintype "passive"))
      (node (ref "U2") (pin "Y12") (pinfunction "VSS_Y12") (pintype "passive"))
      (node (ref "U2") (pin "Y5") (pinfunction "VSS_Y5") (pintype "passive"))
      (node (ref "U2") (pin "Y8") (pinfunction "VSS_Y8") (pintype "passive"))
    )
    (net (code "63") (name "Net-(U2A-ODT_CA_A)") (class "Default")
      (node (ref "R42") (pin "1") (pinfunction "1_1") (pintype "passive"))
      (node (ref "U2") (pin "G2") (pinfunction "ODT_CA_A_G2") (pintype "passive"))
    )
    (net (code "64") (name "Net-(U2A-ODT_CA_B)") (class "Default")
      (node (ref "R43") (pin "2") (pinfunction "2_2") (pintype "passive"))
      (node (ref "U2") (pin "T2") (pinfunction "ODT_CA_B_T2") (pintype "passive"))
    )
    (net (code "65") (name "Net-(U2A-ZQ0)") (class "Default")
      (node (ref "R44") (pin "2") (pinfunction "2_2") (pintype "passive"))
      (node (ref "U2") (pin "A5") (pinfunction "ZQ0_A5") (pintype "passive"))
    )
    (net (code "66") (name "Net-(U2A-ZQ1)") (class "Default")
      (node (ref "R45") (pin "2") (pinfunction "2_2") (pintype "passive"))
      (node (ref "U2") (pin "A8") (pinfunction "ZQ1_A8") (pintype "passive"))
    )
    (net (code "67") (name "VCC1V8_LPDDR4_A") (class "Default")
      (node (ref "C154") (pin "2") (pinfunction "2_2") (pintype "passive"))
      (node (ref "C155") (pin "2") (pinfunction "2_2") (pintype "passive"))
      (node (ref "C156") (pin "2") (pinfunction "2_2") (pintype "passive"))
      (node (ref "C157") (pin "2") (pinfunction "2_2") (pintype "passive"))
      (node (ref "C158") (pin "2") (pinfunction "2_2") (pintype "passive"))
      (node (ref "C159") (pin "2") (pinfunction "2_2") (pintype "passive"))
      (node (ref "C160") (pin "2") (pinfunction "2_2") (pintype "passive"))
      (node (ref "C161") (pin "2") (pinfunction "2_2") (pintype "passive"))
      (node (ref "C162") (pin "2") (pinfunction "2_2") (pintype "passive"))
      (node (ref "FB6") (pin "2") (pinfunction "2_2") (pintype "passive"))
      (node (ref "U2") (pin "F1") (pinfunction "VDD1_F1") (pintype "passive"))
      (node (ref "U2") (pin "F12") (pinfunction "VDD1_F12") (pintype "passive"))
      (node (ref "U2") (pin "G4") (pinfunction "VDD1_G4") (pintype "passive"))
      (node (ref "U2") (pin "G9") (pinfunction "VDD1_G9") (pintype "passive"))
      (node (ref "U2") (pin "T4") (pinfunction "VDD1_T4") (pintype "passive"))
      (node (ref "U2") (pin "T9") (pinfunction "VDD1_T9") (pintype "passive"))
      (node (ref "U2") (pin "U1") (pinfunction "VDD1_U1") (pintype "passive"))
      (node (ref "U2") (pin "U12") (pinfunction "VDD1_U12") (pintype "passive"))
    )
    (net (code "68") (name "VCC_DDR") (class "Default")
      (node (ref "C118") (pin "2") (pinfunction "2_2") (pintype "passive"))
      (node (ref "C119") (pin "2") (pinfunction "2_2") (pintype "passive"))
      (node (ref "C120") (pin "2") (pinfunction "2_2") (pintype "passive"))
      (node (ref "C121") (pin "2") (pinfunction "2_2") (pintype "passive"))
      (node (ref "C122") (pin "2") (pinfunction "2_2") (pintype "passive"))
      (node (ref "C123") (pin "2") (pinfunction "2_2") (pintype "passive"))
      (node (ref "C124") (pin "2") (pinfunction "2_2") (pintype "passive"))
      (node (ref "C125") (pin "2") (pinfunction "2_2") (pintype "passive"))
      (node (ref "C126") (pin "2") (pinfunction "2_2") (pintype "passive"))
      (node (ref "C127") (pin "2") (pinfunction "2_2") (pintype "passive"))
      (node (ref "C128") (pin "2") (pinfunction "2_2") (pintype "passive"))
      (node (ref "C129") (pin "2") (pinfunction "2_2") (pintype "passive"))
      (node (ref "C130") (pin "2") (pinfunction "2_2") (pintype "passive"))
      (node (ref "C131") (pin "2") (pinfunction "2_2") (pintype "passive"))
      (node (ref "C132") (pin "2") (pinfunction "2_2") (pintype "passive"))
      (node (ref "C133") (pin "2") (pinfunction "2_2") (pintype "passive"))
      (node (ref "C134") (pin "2") (pinfunction "2_2") (pintype "passive"))
      (node (ref "C135") (pin "2") (pinfunction "2_2") (pintype "passive"))
      (node (ref "FB6") (pin "1") (pinfunction "1_1") (pintype "passive"))
      (node (ref "U2") (pin "A4") (pinfunction "VDD2_A4") (pintype "passive"))
      (node (ref "U2") (pin "A9") (pinfunction "VDD2_A9") (pintype "passive"))
      (node (ref "U2") (pin "AB4") (pinfunction "VDD2_AB4") (pintype "passive"))
      (node (ref "U2") (pin "AB9") (pinfunction "VDD2_AB9") (pintype "passive"))
      (node (ref "U2") (pin "F5") (pinfunction "VDD2_F5") (pintype "passive"))
      (node (ref "U2") (pin "F8") (pinfunction "VDD2_F8") (pintype "passive"))
      (node (ref "U2") (pin "H1") (pinfunction "VDD2_H1") (pintype "passive"))
      (node (ref "U2") (pin "H12") (pinfunction "VDD2_H12") (pintype "passive"))
      (node (ref "U2") (pin "H5") (pinfunction "VDD2_H5") (pintype "passive"))
      (node (ref "U2") (pin "H8") (pinfunction "VDD2_H8") (pintype "passive"))
      (node (ref "U2") (pin "K1") (pinfunction "VDD2_K1") (pintype "passive"))
      (node (ref "U2") (pin "K10") (pinfunction "VDD2_K10") (pintype "passive"))
      (node (ref "U2") (pin "K12") (pinfunction "VDD2_K12") (pintype "passive"))
      (node (ref "U2") (pin "K3") (pinfunction "VDD2_K3") (pintype "passive"))
      (node (ref "U2") (pin "N1") (pinfunction "VDD2_N1") (pintype "passive"))
      (node (ref "U2") (pin "N10") (pinfunction "VDD2_N10") (pintype "passive"))
      (node (ref "U2") (pin "N12") (pinfunction "VDD2_N12") (pintype "passive"))
      (node (ref "U2") (pin "N3") (pinfunction "VDD2_N3") (pintype "passive"))
      (node (ref "U2") (pin "R1") (pinfunction "VDD2_R1") (pintype "passive"))
      (node (ref "U2") (pin "R12") (pinfunction "VDD2_R12") (pintype "passive"))
      (node (ref "U2") (pin "R5") (pinfunction "VDD2_R5") (pintype "passive"))
      (node (ref "U2") (pin "R8") (pinfunction "VDD2_R8") (pintype "passive"))
      (node (ref "U2") (pin "U5") (pinfunction "VDD2_U5") (pintype "passive"))
      (node (ref "U2") (pin "U8") (pinfunction "VDD2_U8") (pintype "passive"))
    )
    (net (code "69") (name "VCC_DDRC") (class "Default")
      (node (ref "C136") (pin "2") (pinfunction "2_2") (pintype "passive"))
      (node (ref "C137") (pin "2") (pinfunction "2_2") (pintype "passive"))
      (node (ref "C138") (pin "2") (pinfunction "2_2") (pintype "passive"))
      (node (ref "C139") (pin "2") (pinfunction "2_2") (pintype "passive"))
      (node (ref "C140") (pin "2") (pinfunction "2_2") (pintype "passive"))
      (node (ref "C141") (pin "2") (pinfunction "2_2") (pintype "passive"))
      (node (ref "C142") (pin "2") (pinfunction "2_2") (pintype "passive"))
      (node (ref "C143") (pin "2") (pinfunction "2_2") (pintype "passive"))
      (node (ref "C144") (pin "2") (pinfunction "2_2") (pintype "passive"))
      (node (ref "C145") (pin "2") (pinfunction "2_2") (pintype "passive"))
      (node (ref "C146") (pin "2") (pinfunction "2_2") (pintype "passive"))
      (node (ref "C147") (pin "2") (pinfunction "2_2") (pintype "passive"))
      (node (ref "C148") (pin "2") (pinfunction "2_2") (pintype "passive"))
      (node (ref "C149") (pin "2") (pinfunction "2_2") (pintype "passive"))
      (node (ref "C150") (pin "2") (pinfunction "2_2") (pintype "passive"))
      (node (ref "C151") (pin "2") (pinfunction "2_2") (pintype "passive"))
      (node (ref "C152") (pin "2") (pinfunction "2_2") (pintype "passive"))
      (node (ref "C153") (pin "2") (pinfunction "2_2") (pintype "passive"))
      (node (ref "R42") (pin "2") (pinfunction "2_2") (pintype "passive"))
      (node (ref "R44") (pin "1") (pinfunction "1_1") (pintype "passive"))
      (node (ref "R45") (pin "1") (pinfunction "1_1") (pintype "passive"))
      (node (ref "U2") (pin "AA10") (pinfunction "VDDQ_AA10") (pintype "passive"))
      (node (ref "U2") (pin "AA3") (pinfunction "VDDQ_AA3") (pintype "passive"))
      (node (ref "U2") (pin "AA5") (pinfunction "VDDQ_AA5") (pintype "passive"))
      (node (ref "U2") (pin "AA8") (pinfunction "VDDQ_AA8") (pintype "passive"))
      (node (ref "U2") (pin "B10") (pinfunction "VDDQ_B10") (pintype "passive"))
      (node (ref "U2") (pin "B3") (pinfunction "VDDQ_B3") (pintype "passive"))
      (node (ref "U2") (pin "B5") (pinfunction "VDDQ_B5") (pintype "passive"))
      (node (ref "U2") (pin "B8") (pinfunction "VDDQ_B8") (pintype "passive"))
      (node (ref "U2") (pin "D1") (pinfunction "VDDQ_D1") (pintype "passive"))
      (node (ref "U2") (pin "D12") (pinfunction "VDDQ_D12") (pintype "passive"))
      (node (ref "U2") (pin "D5") (pinfunction "VDDQ_D5") (pintype "passive"))
      (node (ref "U2") (pin "D8") (pinfunction "VDDQ_D8") (pintype "passive"))
      (node (ref "U2") (pin "F10") (pinfunction "VDDQ_F10") (pintype "passive"))
      (node (ref "U2") (pin "F3") (pinfunction "VDDQ_F3") (pintype "passive"))
      (node (ref "U2") (pin "U10") (pinfunction "VDDQ_U10") (pintype "passive"))
      (node (ref "U2") (pin "U3") (pinfunction "VDDQ_U3") (pintype "passive"))
      (node (ref "U2") (pin "W1") (pinfunction "VDDQ_W1") (pintype "passive"))
      (node (ref "U2") (pin "W12") (pinfunction "VDDQ_W12") (pintype "passive"))
      (node (ref "U2") (pin "W5") (pinfunction "VDDQ_W5") (pintype "passive"))
      (node (ref "U2") (pin "W8") (pinfunction "VDDQ_W8") (pintype "passive"))
    )
    (net (code "70") (name "unconnected-(U2B-DNU1-PadA1)") (class "Default")
      (node (ref "U2") (pin "A1") (pinfunction "DNU1_A1") (pintype "passive+no_connect"))
    )
    (net (code "71") (name "unconnected-(U2B-DNU2-PadA2)") (class "Default")
      (node (ref "U2") (pin "A2") (pinfunction "DNU2_A2") (pintype "passive+no_connect"))
    )
    (net (code "72") (name "unconnected-(U2B-DNU3-PadA11)") (class "Default")
      (node (ref "U2") (pin "A11") (pinfunction "DNU3_A11") (pintype "passive+no_connect"))
    )
    (net (code "73") (name "unconnected-(U2B-DNU4-PadA12)") (class "Default")
      (node (ref "U2") (pin "A12") (pinfunction "DNU4_A12") (pintype "passive+no_connect"))
    )
    (net (code "74") (name "unconnected-(U2B-DNU5-PadB1)") (class "Default")
      (node (ref "U2") (pin "B1") (pinfunction "DNU5_B1") (pintype "passive+no_connect"))
    )
    (net (code "75") (name "unconnected-(U2B-DNU6-PadB12)") (class "Default")
      (node (ref "U2") (pin "B12") (pinfunction "DNU6_B12") (pintype "passive+no_connect"))
    )
    (net (code "76") (name "unconnected-(U2B-DNU7-PadAA1)") (class "Default")
      (node (ref "U2") (pin "AA1") (pinfunction "DNU7_AA1") (pintype "passive+no_connect"))
    )
    (net (code "77") (name "unconnected-(U2B-DNU8-PadAA12)") (class "Default")
      (node (ref "U2") (pin "AA12") (pinfunction "DNU8_AA12") (pintype "passive+no_connect"))
    )
    (net (code "78") (name "unconnected-(U2B-DNU9-PadAB1)") (class "Default")
      (node (ref "U2") (pin "AB1") (pinfunction "DNU9_AB1") (pintype "passive+no_connect"))
    )
    (net (code "79") (name "unconnected-(U2B-DNU10-PadAB2)") (class "Default")
      (node (ref "U2") (pin "AB2") (pinfunction "DNU10_AB2") (pintype "passive+no_connect"))
    )
    (net (code "80") (name "unconnected-(U2B-DNU11-PadAB11)") (class "Default")
      (node (ref "U2") (pin "AB11") (pinfunction "DNU11_AB11") (pintype "passive+no_connect"))
    )
    (net (code "81") (name "unconnected-(U2B-DNU12-PadAB12)") (class "Default")
      (node (ref "U2") (pin "AB12") (pinfunction "DNU12_AB12") (pintype "passive+no_connect"))
    )
    (net (code "82") (name "unconnected-(U2B-DNU13-PadK8)") (class "Default")
      (node (ref "U2") (pin "K8") (pinfunction "DNU13_K8") (pintype "passive+no_connect"))
    )
    (net (code "83") (name "unconnected-(U2B-DNU14-PadN5)") (class "Default")
      (node (ref "U2") (pin "N5") (pinfunction "DNU14_N5") (pintype "passive+no_connect"))
    )
    (net (code "84") (name "unconnected-(U2B-DNU15-PadK5)") (class "Default")
      (node (ref "U2") (pin "K5") (pinfunction "DNU15_K5") (pintype "passive+no_connect"))
    )
    (net (code "85") (name "unconnected-(U2B-DNU16-PadG11)") (class "Default")
      (node (ref "U2") (pin "G11") (pinfunction "DNU16_G11") (pintype "passive+no_connect"))
    )
    (net (code "86") (name "unconnected-(U2B-DNU17-PadN8)") (class "Default")
      (node (ref "U2") (pin "N8") (pinfunction "DNU17_N8") (pintype "passive+no_connect"))
    )
  )
)
